# WBV2-final.net
KiCad netlist of a schematic drawn in EAGLE
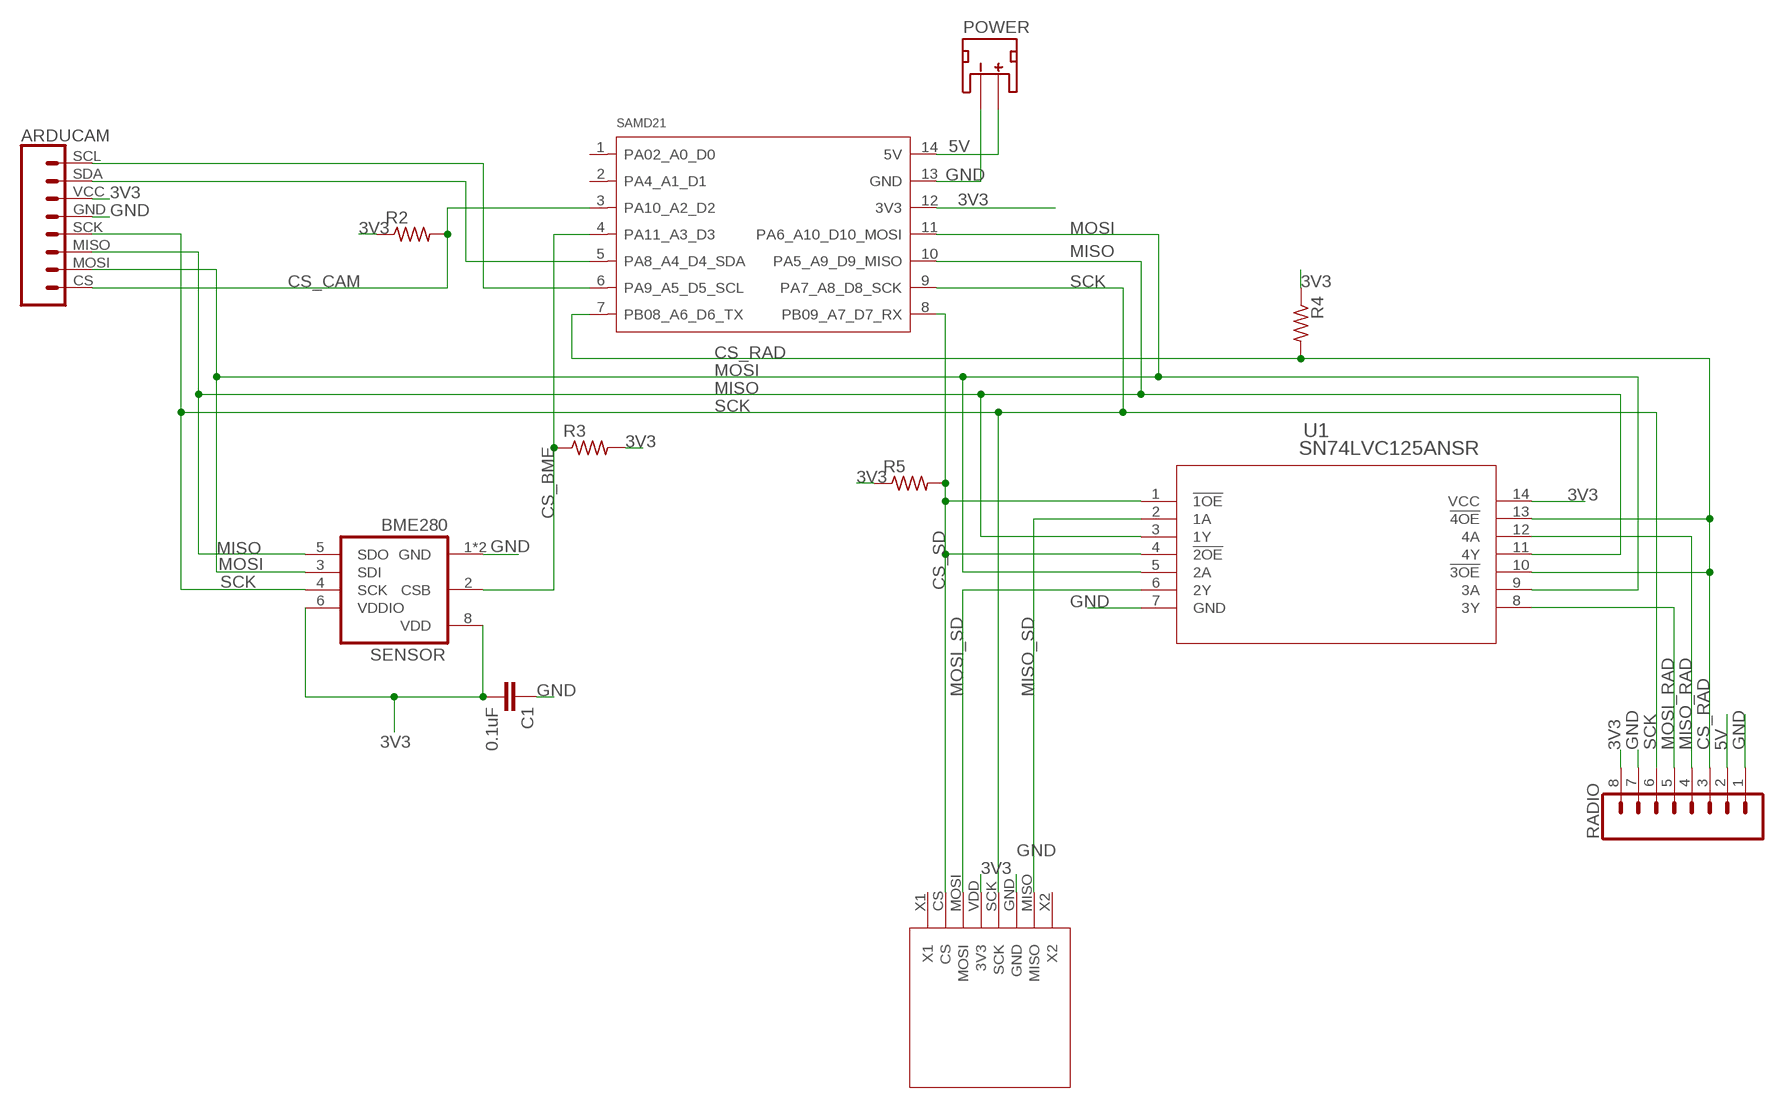
[diagram p0: schematic, sheet 1]

(export (version "E")
  (design (tool "Eeschema 10.0.6"))
  (components
    (comp (ref "C1")
      (value "0.1uF")
      (footprint "eagle-import:0402")
      (libsource (lib "eagle-import") (part "0.1UF-0402-16V-10%"))
    )
    (comp (ref "CAM")
      (value "ARDUCAM_MINI")
      (footprint "eagle-import:ARDUCAM_MINI")
      (libsource (lib "eagle-import") (part "ARDUCAM_MINI"))
    )
    (comp (ref "POWER")
      (value "JST_2MM_MALE")
      (footprint "eagle-import:JST-2-SMD")
      (libsource (lib "eagle-import") (part "JST_2MM_MALE"))
    )
    (comp (ref "R2")
      (value "R-US_R0402")
      (footprint "eagle-import:R0402")
      (libsource (lib "eagle-import") (part "R-US_R0402"))
    )
    (comp (ref "R3")
      (value "R-US_R0402")
      (footprint "eagle-import:R0402")
      (libsource (lib "eagle-import") (part "R-US_R0402"))
    )
    (comp (ref "R4")
      (value "R-US_R0402")
      (footprint "eagle-import:R0402")
      (libsource (lib "eagle-import") (part "R-US_R0402"))
    )
    (comp (ref "R5")
      (value "R-US_R0402")
      (footprint "eagle-import:R0402")
      (libsource (lib "eagle-import") (part "R-US_R0402"))
    )
    (comp (ref "RADIO")
      (value "CONN_08\"")
      (footprint "eagle-import:1X08")
      (libsource (lib "eagle-import") (part "CONN_08{dblquote}"))
    )
    (comp (ref "SAMD21")
      (value "MOUDLE-SEEEDUINO-XIAO")
      (footprint "eagle-import:MOUDLE14P-2.54-21X17.8MM")
      (libsource (lib "eagle-import") (part "MOUDLE-SEEEDUINO-XIAO"))
    )
    (comp (ref "SD")
      (value "SD_READER")
      (footprint "eagle-import:SDREAD")
      (libsource (lib "eagle-import") (part "SD_READER"))
    )
    (comp (ref "SENSOR")
      (value "BME280")
      (footprint "eagle-import:BME280")
      (libsource (lib "eagle-import") (part "BME280"))
    )
    (comp (ref "U1")
      (value "SN74LVC125ANSR")
      (footprint "eagle-import:NS14")
      (fields (field (name "COPYRIGHT") "Copyright (C) 2024 Ultra Librarian. All rights reserved."))
      (libsource (lib "eagle-import") (part "SN74LVC125ANSR"))
    )
  )
  (nets
    (net (code "1") (name "/3V3") (class "Default")
      (node (ref "C1") (pin "2") (pinfunction "2_2") (pintype "passive"))
      (node (ref "CAM") (pin "VCC") (pinfunction "VCC_VCC") (pintype "passive"))
      (node (ref "R2") (pin "1") (pinfunction "1_1") (pintype "passive"))
      (node (ref "R3") (pin "2") (pinfunction "2_2") (pintype "passive"))
      (node (ref "R4") (pin "1") (pinfunction "1_1") (pintype "passive"))
      (node (ref "R5") (pin "1") (pinfunction "1_1") (pintype "passive"))
      (node (ref "RADIO") (pin "8") (pinfunction "8_8") (pintype "passive"))
      (node (ref "SAMD21") (pin "12") (pinfunction "3V3_12") (pintype "bidirectional"))
      (node (ref "SD") (pin "VDD") (pinfunction "3V3_VDD") (pintype "bidirectional"))
      (node (ref "SENSOR") (pin "6") (pinfunction "VDDIO_6") (pintype "power_in"))
      (node (ref "SENSOR") (pin "8") (pinfunction "VDD_8") (pintype "power_in"))
      (node (ref "U1") (pin "14") (pinfunction "VCC_14") (pintype "power_in"))
    )
    (net (code "2") (name "/5V") (class "Default")
      (node (ref "POWER") (pin "2") (pinfunction "+_2") (pintype "bidirectional"))
      (node (ref "RADIO") (pin "2") (pinfunction "2_2") (pintype "passive"))
      (node (ref "SAMD21") (pin "14") (pinfunction "5V_14") (pintype "bidirectional"))
    )
    (net (code "3") (name "/CS_BME") (class "Default")
      (node (ref "R3") (pin "1") (pinfunction "1_1") (pintype "passive"))
      (node (ref "SAMD21") (pin "4") (pinfunction "PA11_A3_D3_4") (pintype "bidirectional"))
      (node (ref "SENSOR") (pin "2") (pinfunction "CSB_2") (pintype "input"))
    )
    (net (code "4") (name "/CS_CAM") (class "Default")
      (node (ref "CAM") (pin "CS") (pinfunction "CS_CS") (pintype "passive"))
      (node (ref "R2") (pin "2") (pinfunction "2_2") (pintype "passive"))
      (node (ref "SAMD21") (pin "3") (pinfunction "PA10_A2_D2_3") (pintype "bidirectional"))
    )
    (net (code "5") (name "/CS_RAD") (class "Default")
      (node (ref "R4") (pin "2") (pinfunction "2_2") (pintype "passive"))
      (node (ref "RADIO") (pin "3") (pinfunction "3_3") (pintype "passive"))
      (node (ref "SAMD21") (pin "7") (pinfunction "PB08_A6_D6_TX_7") (pintype "bidirectional"))
      (node (ref "U1") (pin "10") (pinfunction "~{3OE}_10") (pintype "input"))
      (node (ref "U1") (pin "13") (pinfunction "~{4OE}_13") (pintype "input"))
    )
    (net (code "6") (name "/CS_SD") (class "Default")
      (node (ref "R5") (pin "2") (pinfunction "2_2") (pintype "passive"))
      (node (ref "SAMD21") (pin "8") (pinfunction "PB09_A7_D7_RX_8") (pintype "bidirectional"))
      (node (ref "SD") (pin "CS") (pinfunction "CS_CS") (pintype "bidirectional"))
      (node (ref "U1") (pin "1") (pinfunction "~{1OE}_1") (pintype "input"))
      (node (ref "U1") (pin "4") (pinfunction "~{2OE}_4") (pintype "input"))
    )
    (net (code "7") (name "/GND") (class "Default")
      (node (ref "C1") (pin "1") (pinfunction "1_1") (pintype "passive"))
      (node (ref "CAM") (pin "GND") (pinfunction "GND_GND") (pintype "passive"))
      (node (ref "POWER") (pin "1") (pinfunction "-_1") (pintype "bidirectional"))
      (node (ref "RADIO") (pin "1") (pinfunction "1_1") (pintype "passive"))
      (node (ref "RADIO") (pin "7") (pinfunction "7_7") (pintype "passive"))
      (node (ref "SAMD21") (pin "13") (pinfunction "GND_13") (pintype "bidirectional"))
      (node (ref "SD") (pin "GND") (pinfunction "GND_GND") (pintype "bidirectional"))
      (node (ref "SENSOR") (pin "1") (pinfunction "GND_1") (pintype "power_in"))
      (node (ref "SENSOR") (pin "7") (pinfunction "GND_7") (pintype "power_in"))
      (node (ref "U1") (pin "7") (pinfunction "GND_7") (pintype "power_in"))
    )
    (net (code "8") (name "/MISO") (class "Default")
      (node (ref "CAM") (pin "MISO") (pinfunction "MISO_MISO") (pintype "passive"))
      (node (ref "SAMD21") (pin "10") (pinfunction "PA5_A9_D9_MISO_10") (pintype "bidirectional"))
      (node (ref "SENSOR") (pin "5") (pinfunction "SDO_5") (pintype "input"))
      (node (ref "U1") (pin "11") (pinfunction "4Y_11") (pintype "output"))
      (node (ref "U1") (pin "3") (pinfunction "1Y_3") (pintype "output"))
    )
    (net (code "9") (name "/MISO_RAD") (class "Default")
      (node (ref "RADIO") (pin "4") (pinfunction "4_4") (pintype "passive"))
      (node (ref "U1") (pin "12") (pinfunction "4A_12") (pintype "input"))
    )
    (net (code "10") (name "/MISO_SD") (class "Default")
      (node (ref "SD") (pin "MISO") (pinfunction "MISO_MISO") (pintype "bidirectional"))
      (node (ref "U1") (pin "2") (pinfunction "1A_2") (pintype "input"))
    )
    (net (code "11") (name "/MOSI") (class "Default")
      (node (ref "CAM") (pin "MOSI") (pinfunction "MOSI_MOSI") (pintype "passive"))
      (node (ref "SAMD21") (pin "11") (pinfunction "PA6_A10_D10_MOSI_11") (pintype "bidirectional"))
      (node (ref "SENSOR") (pin "3") (pinfunction "SDI_3") (pintype "bidirectional"))
      (node (ref "U1") (pin "5") (pinfunction "2A_5") (pintype "input"))
      (node (ref "U1") (pin "9") (pinfunction "3A_9") (pintype "input"))
    )
    (net (code "12") (name "/MOSI_RAD") (class "Default")
      (node (ref "RADIO") (pin "5") (pinfunction "5_5") (pintype "passive"))
      (node (ref "U1") (pin "8") (pinfunction "3Y_8") (pintype "output"))
    )
    (net (code "13") (name "/MOSI_SD") (class "Default")
      (node (ref "SD") (pin "MOSI") (pinfunction "MOSI_MOSI") (pintype "bidirectional"))
      (node (ref "U1") (pin "6") (pinfunction "2Y_6") (pintype "output"))
    )
    (net (code "14") (name "/SCK") (class "Default")
      (node (ref "CAM") (pin "SCK") (pinfunction "SCK_SCK") (pintype "passive"))
      (node (ref "RADIO") (pin "6") (pinfunction "6_6") (pintype "passive"))
      (node (ref "SAMD21") (pin "9") (pinfunction "PA7_A8_D8_SCK_9") (pintype "bidirectional"))
      (node (ref "SD") (pin "SCK") (pinfunction "SCK_SCK") (pintype "bidirectional"))
      (node (ref "SENSOR") (pin "4") (pinfunction "SCK_4") (pintype "bidirectional"))
    )
    (net (code "15") (name "Net-(SAMD21-PA8_A4_D4_SDA)") (class "Default")
      (node (ref "CAM") (pin "SDA") (pinfunction "SDA_SDA") (pintype "passive"))
      (node (ref "SAMD21") (pin "5") (pinfunction "PA8_A4_D4_SDA_5") (pintype "bidirectional"))
    )
    (net (code "16") (name "Net-(SAMD21-PA9_A5_D5_SCL)") (class "Default")
      (node (ref "CAM") (pin "SCL") (pinfunction "SCL_SCL") (pintype "passive"))
      (node (ref "SAMD21") (pin "6") (pinfunction "PA9_A5_D5_SCL_6") (pintype "bidirectional"))
    )
    (net (code "17") (name "unconnected-(POWER-PAD1-PadNC1)") (class "Default")
      (node (ref "POWER") (pin "NC1") (pinfunction "PAD1_NC1") (pintype "bidirectional"))
    )
    (net (code "18") (name "unconnected-(POWER-PAD2-PadNC2)") (class "Default")
      (node (ref "POWER") (pin "NC2") (pinfunction "PAD2_NC2") (pintype "bidirectional"))
    )
    (net (code "19") (name "unconnected-(SAMD21-PA02_A0_D0-Pad1)") (class "Default")
      (node (ref "SAMD21") (pin "1") (pinfunction "PA02_A0_D0_1") (pintype "bidirectional"))
    )
    (net (code "20") (name "unconnected-(SAMD21-PA4_A1_D1-Pad2)") (class "Default")
      (node (ref "SAMD21") (pin "2") (pinfunction "PA4_A1_D1_2") (pintype "bidirectional"))
    )
    (net (code "21") (name "unconnected-(SD-PadX1)") (class "Default")
      (node (ref "SD") (pin "X1") (pinfunction "X1_X1") (pintype "bidirectional"))
    )
    (net (code "22") (name "unconnected-(SD-PadX2)") (class "Default")
      (node (ref "SD") (pin "X2") (pinfunction "X2_X2") (pintype "bidirectional"))
    )
  )
)
